# Bela_fan_control.net
KiCad netlist of a schematic drawn in Altium Designer
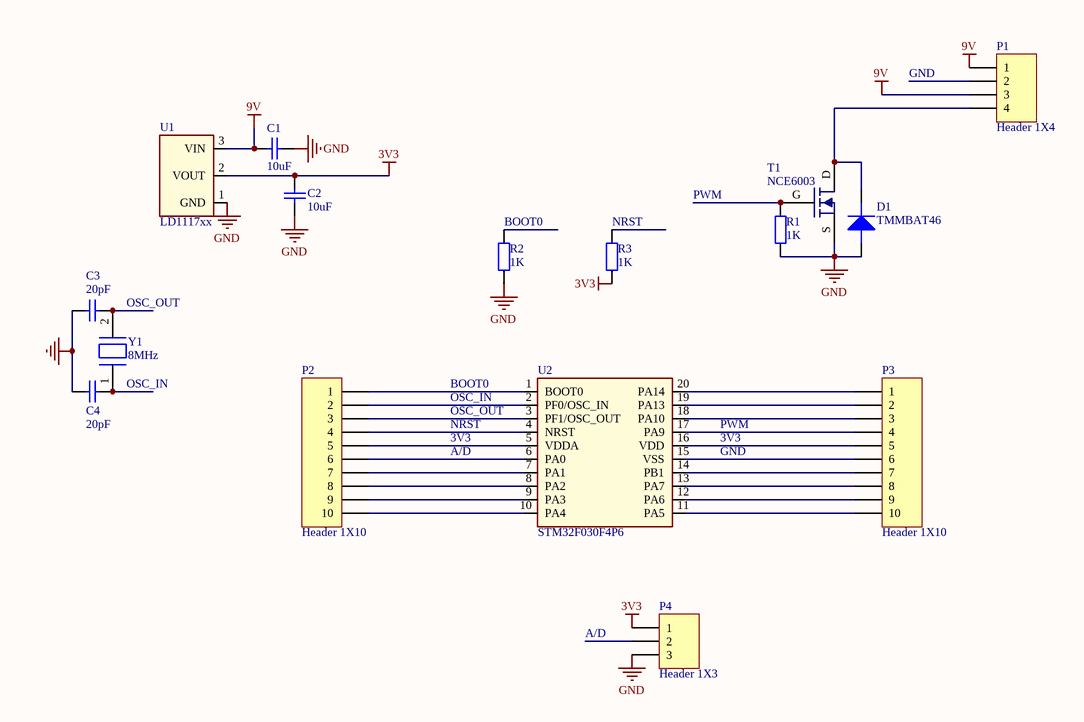
[diagram p0: Bela_fan_control.SchDoc]

(export (version "E")
  (design (tool "Eeschema 10.0.6"))
  (components
    (comp (ref "C1")
      (value "10uF")
      (footprint "FP_1206_CAP_085")
      (description "Capacitor ceramic X7R")
      (libsource (lib "Capacitor") (part "Cap"))
    )
    (comp (ref "C2")
      (value "10uF")
      (footprint "FP_1206_CAP_085")
      (description "Capacitor ceramic X7R")
      (libsource (lib "Capacitor") (part "Cap"))
    )
    (comp (ref "C3")
      (value "20pF")
      (footprint "FP_0603_CAP_080")
      (description "Capacitor")
      (fields (field (name "PART NUMBER") "20pF_0603_50V_NP0_5percent"))
      (libsource (lib "Miscellaneous Devices") (part "Cap"))
    )
    (comp (ref "C4")
      (value "20pF")
      (footprint "FP_0603_CAP_080")
      (description "Capacitor")
      (fields (field (name "PART NUMBER") "20pF_0603_50V_NP0_5percent"))
      (libsource (lib "Miscellaneous Devices") (part "Cap"))
    )
    (comp (ref "D1")
      (value "TMMBAT46")
      (footprint "SOD-80")
      (fields (field (name "PART NUMBER") "TMMBAT46FILM"))
      (libsource (lib "Diode") (part "DIODE_big"))
    )
    (comp (ref "P1")
      (value "Header 1X4")
      (footprint "HEADER_2.54MM_M_1x4")
      (description "Header, 4-Pin")
      (fields (field (name "PUBLISHER") "Altium Limited"))
      (libsource (lib "Header") (part "Header 1X4"))
    )
    (comp (ref "P2")
      (value "Header 1X10")
      (footprint "HEADER_2.54MM_M_1x10")
      (description "Header, 10-Pin")
      (fields (field (name "PUBLISHER") "Altium Limited"))
      (libsource (lib "") (part "Header 1X10_1"))
    )
    (comp (ref "P3")
      (value "Header 1X10")
      (footprint "HEADER_2.54MM_M_1x10")
      (description "Header, 10-Pin")
      (fields (field (name "PUBLISHER") "Altium Limited"))
      (libsource (lib "Header") (part "Header 1X10"))
    )
    (comp (ref "P4")
      (value "Header 1X3")
      (footprint "HEADER_2.54MM_M_1x3")
      (description "Header, 3-Pin")
      (fields (field (name "PUBLISHER") "Altium Limited"))
      (libsource (lib "Header") (part "Header 1X3"))
    )
    (comp (ref "R1")
      (value "1K")
      (footprint "FP_0603_RES")
      (description "Resistor")
      (fields (field (name "PART NUMBER") "1k_0603_1percent"))
      (libsource (lib "Resistor") (part "RES"))
    )
    (comp (ref "R2")
      (value "1K")
      (footprint "FP_0603_RES")
      (description "Resistor")
      (fields (field (name "PART NUMBER") "1k_0603_1percent"))
      (libsource (lib "Resistor") (part "RES"))
    )
    (comp (ref "R3")
      (value "1K")
      (footprint "FP_0603_RES")
      (description "Resistor")
      (fields (field (name "PART NUMBER") "1k_0603_1percent"))
      (libsource (lib "Resistor") (part "RES"))
    )
    (comp (ref "T1")
      (value "NCE6003")
      (footprint "FET_SOT23")
      (description "N Channel 60V 3A 2V @ 250uA 105 mΩ @ 3A,10V 1.7W SOT-23(SOT-23-3) MOSFET RoHS")
      (libsource (lib "FET") (part "NMOS"))
    )
    (comp (ref "U1")
      (value "LD1117xx")
      (footprint "SUPPLY_SOT223")
      (description "LD1117xx 3,3V lin reg")
      (libsource (lib "Supply") (part "LD1117xx"))
    )
    (comp (ref "U2")
      (value "STM32F030F4P6")
      (footprint "uC_TSSOP20")
      (libsource (lib "uC") (part "STM32F030F4P6"))
    )
    (comp (ref "Y1")
      (value "8MHz")
      (footprint "FP_CRYSTAL_HC49_SMD")
      (description "Quartz")
      (libsource (lib "Quartz") (part "XTAL"))
    )
  )
  (nets
    (net (code "1") (name "/A{slash}D") (class "Default")
      (node (ref "P2") (pin "6") (pinfunction "6_6") (pintype "passive"))
      (node (ref "P4") (pin "2") (pinfunction "2_2") (pintype "passive"))
      (node (ref "U2") (pin "6") (pinfunction "PA0_6") (pintype "passive"))
    )
    (net (code "2") (name "/BOOT0") (class "Default")
      (node (ref "P2") (pin "1") (pinfunction "1_1") (pintype "passive"))
      (node (ref "R2") (pin "1") (pinfunction "1_1") (pintype "passive"))
      (node (ref "U2") (pin "1") (pinfunction "BOOT0_1") (pintype "passive"))
    )
    (net (code "3") (name "/NRST") (class "Default")
      (node (ref "P2") (pin "4") (pinfunction "4_4") (pintype "passive"))
      (node (ref "R3") (pin "1") (pinfunction "1_1") (pintype "passive"))
      (node (ref "U2") (pin "4") (pinfunction "NRST_4") (pintype "passive"))
    )
    (net (code "4") (name "/OSC_IN") (class "Default")
      (node (ref "C4") (pin "2") (pinfunction "2_2") (pintype "passive"))
      (node (ref "P2") (pin "2") (pinfunction "2_2") (pintype "passive"))
      (node (ref "U2") (pin "2") (pinfunction "PF0/OSC_IN_2") (pintype "passive"))
      (node (ref "Y1") (pin "1") (pinfunction "1_1") (pintype "passive"))
    )
    (net (code "5") (name "/OSC_OUT") (class "Default")
      (node (ref "C3") (pin "2") (pinfunction "2_2") (pintype "passive"))
      (node (ref "P2") (pin "3") (pinfunction "3_3") (pintype "passive"))
      (node (ref "U2") (pin "3") (pinfunction "PF1/OSC_OUT_3") (pintype "passive"))
      (node (ref "Y1") (pin "2") (pinfunction "2_2") (pintype "passive"))
    )
    (net (code "6") (name "/PWM") (class "Default")
      (node (ref "P3") (pin "4") (pinfunction "4_4") (pintype "passive"))
      (node (ref "R1") (pin "1") (pinfunction "1_1") (pintype "passive"))
      (node (ref "T1") (pin "G") (pinfunction "G_G") (pintype "passive"))
      (node (ref "U2") (pin "17") (pinfunction "PA9_17") (pintype "passive"))
    )
    (net (code "7") (name "3V3") (class "Default")
      (node (ref "C2") (pin "2") (pinfunction "2_2") (pintype "passive"))
      (node (ref "P2") (pin "5") (pinfunction "5_5") (pintype "passive"))
      (node (ref "P3") (pin "5") (pinfunction "5_5") (pintype "passive"))
      (node (ref "P4") (pin "1") (pinfunction "1_1") (pintype "passive"))
      (node (ref "R3") (pin "2") (pinfunction "2_2") (pintype "passive"))
      (node (ref "U1") (pin "2") (pinfunction "VOUT_2") (pintype "passive"))
      (node (ref "U2") (pin "16") (pinfunction "VDD_16") (pintype "passive"))
      (node (ref "U2") (pin "5") (pinfunction "VDDA_5") (pintype "passive"))
    )
    (net (code "8") (name "9V") (class "Default")
      (node (ref "C1") (pin "2") (pinfunction "2_2") (pintype "passive"))
      (node (ref "P1") (pin "1") (pinfunction "1_1") (pintype "passive"))
      (node (ref "P1") (pin "3") (pinfunction "3_3") (pintype "passive"))
      (node (ref "U1") (pin "3") (pinfunction "VIN_3") (pintype "passive"))
    )
    (net (code "9") (name "GND") (class "Default")
      (node (ref "C1") (pin "1") (pinfunction "1_1") (pintype "passive"))
      (node (ref "C2") (pin "1") (pinfunction "1_1") (pintype "passive"))
      (node (ref "C3") (pin "1") (pinfunction "1_1") (pintype "passive"))
      (node (ref "C4") (pin "1") (pinfunction "1_1") (pintype "passive"))
      (node (ref "D1") (pin "A") (pinfunction "A_A") (pintype "passive"))
      (node (ref "P1") (pin "2") (pinfunction "2_2") (pintype "passive"))
      (node (ref "P3") (pin "6") (pinfunction "6_6") (pintype "passive"))
      (node (ref "P4") (pin "3") (pinfunction "3_3") (pintype "passive"))
      (node (ref "R1") (pin "2") (pinfunction "2_2") (pintype "passive"))
      (node (ref "R2") (pin "2") (pinfunction "2_2") (pintype "passive"))
      (node (ref "T1") (pin "S") (pinfunction "S_S") (pintype "passive"))
      (node (ref "U1") (pin "1") (pinfunction "GND_1") (pintype "passive"))
      (node (ref "U2") (pin "15") (pinfunction "VSS_15") (pintype "passive"))
    )
    (net (code "10") (name "Net-(D1-PadK)") (class "Default")
      (node (ref "D1") (pin "K") (pinfunction "K_K") (pintype "passive"))
      (node (ref "P1") (pin "4") (pinfunction "4_4") (pintype "passive"))
      (node (ref "T1") (pin "D") (pinfunction "D_D") (pintype "passive"))
    )
    (net (code "11") (name "Net-(U2-PA1)") (class "Default")
      (node (ref "P2") (pin "7") (pinfunction "7_7") (pintype "passive"))
      (node (ref "U2") (pin "7") (pinfunction "PA1_7") (pintype "passive"))
    )
    (net (code "12") (name "Net-(U2-PA2)") (class "Default")
      (node (ref "P2") (pin "8") (pinfunction "8_8") (pintype "passive"))
      (node (ref "U2") (pin "8") (pinfunction "PA2_8") (pintype "passive"))
    )
    (net (code "13") (name "Net-(U2-PA3)") (class "Default")
      (node (ref "P2") (pin "9") (pinfunction "9_9") (pintype "passive"))
      (node (ref "U2") (pin "9") (pinfunction "PA3_9") (pintype "passive"))
    )
    (net (code "14") (name "Net-(U2-PA4)") (class "Default")
      (node (ref "P2") (pin "10") (pinfunction "10_10") (pintype "passive"))
      (node (ref "U2") (pin "10") (pinfunction "PA4_10") (pintype "passive"))
    )
    (net (code "15") (name "Net-(U2-PA5)") (class "Default")
      (node (ref "P3") (pin "10") (pinfunction "10_10") (pintype "passive"))
      (node (ref "U2") (pin "11") (pinfunction "PA5_11") (pintype "passive"))
    )
    (net (code "16") (name "Net-(U2-PA6)") (class "Default")
      (node (ref "P3") (pin "9") (pinfunction "9_9") (pintype "passive"))
      (node (ref "U2") (pin "12") (pinfunction "PA6_12") (pintype "passive"))
    )
    (net (code "17") (name "Net-(U2-PA7)") (class "Default")
      (node (ref "P3") (pin "8") (pinfunction "8_8") (pintype "passive"))
      (node (ref "U2") (pin "13") (pinfunction "PA7_13") (pintype "passive"))
    )
    (net (code "18") (name "Net-(U2-PA10)") (class "Default")
      (node (ref "P3") (pin "3") (pinfunction "3_3") (pintype "passive"))
      (node (ref "U2") (pin "18") (pinfunction "PA10_18") (pintype "passive"))
    )
    (net (code "19") (name "Net-(U2-PA13)") (class "Default")
      (node (ref "P3") (pin "2") (pinfunction "2_2") (pintype "passive"))
      (node (ref "U2") (pin "19") (pinfunction "PA13_19") (pintype "passive"))
    )
    (net (code "20") (name "Net-(U2-PA14)") (class "Default")
      (node (ref "P3") (pin "1") (pinfunction "1_1") (pintype "passive"))
      (node (ref "U2") (pin "20") (pinfunction "PA14_20") (pintype "passive"))
    )
    (net (code "21") (name "Net-(U2-PB1)") (class "Default")
      (node (ref "P3") (pin "7") (pinfunction "7_7") (pintype "passive"))
      (node (ref "U2") (pin "14") (pinfunction "PB1_14") (pintype "passive"))
    )
  )
)
